# Board_760032v2.net
KiCad netlist of a schematic drawn in EAGLE
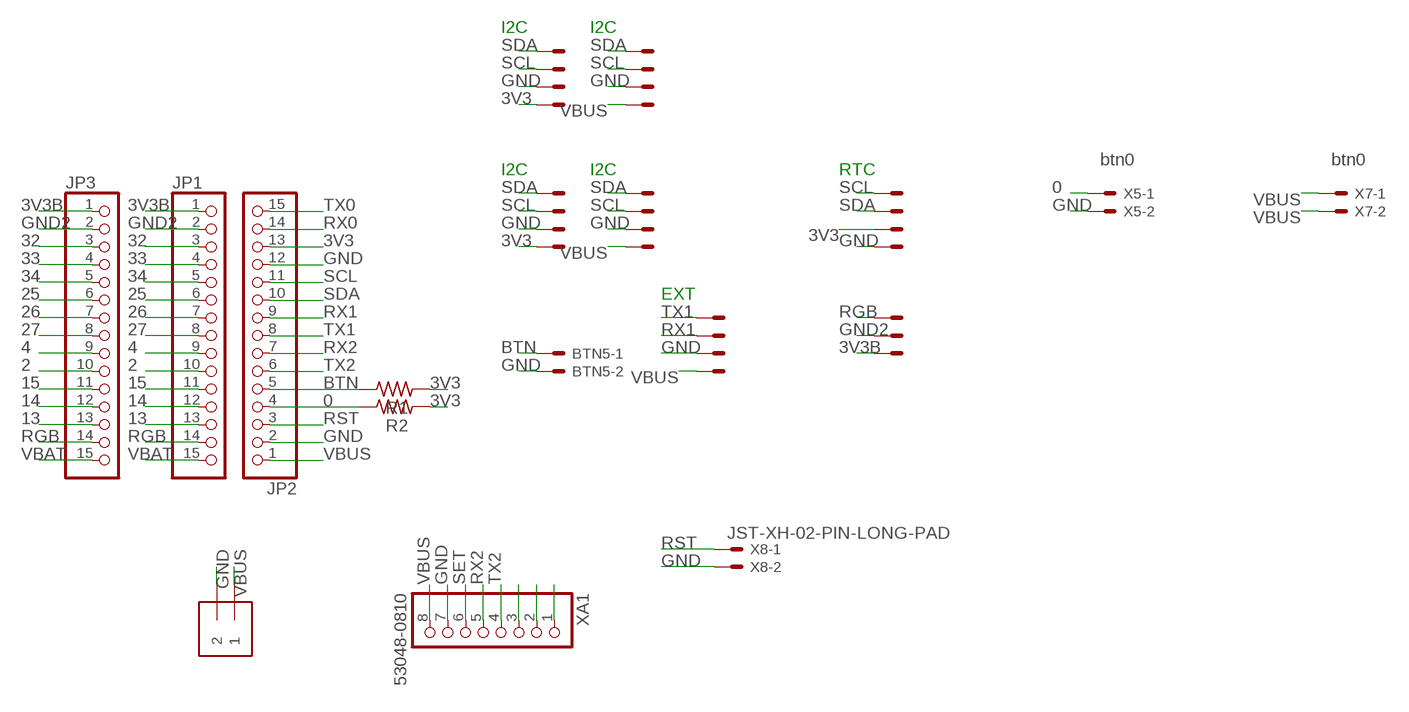
[diagram p0: schematic, sheet 1]

(export (version "E")
  (design (tool "Eeschema 10.0.6"))
  (components
    (comp (ref "BTN5")
      (value "JST-XH-02-PIN-LONG-PAD")
      (footprint "eagle-import:JST-XH-02-PACKAGE-LONG-PAD")
      (libsource (lib "eagle-import") (part "JST-XH-02-PIN-LONG-PAD"))
    )
    (comp (ref "J1")
      (value "1X2-3.5MM")
      (footprint "eagle-import:1X2-3.5MM")
      (libsource (lib "eagle-import") (part "1X2-3.5MM"))
    )
    (comp (ref "JP1")
      (value "PINHD-1X15")
      (footprint "eagle-import:1X15")
      (libsource (lib "eagle-import") (part "PINHD-1X15"))
    )
    (comp (ref "JP2")
      (value "PINHD-1X15")
      (footprint "eagle-import:1X15")
      (libsource (lib "eagle-import") (part "PINHD-1X15"))
    )
    (comp (ref "JP3")
      (value "PINHD-1X15")
      (footprint "eagle-import:1X15")
      (libsource (lib "eagle-import") (part "PINHD-1X15"))
    )
    (comp (ref "R1")
      (value "R-US_0207/7")
      (footprint "eagle-import:0207_7")
      (libsource (lib "eagle-import") (part "R-US_0207/7"))
    )
    (comp (ref "R2")
      (value "R-US_0207/7")
      (footprint "eagle-import:0207_7")
      (libsource (lib "eagle-import") (part "R-US_0207/7"))
    )
    (comp (ref "RTC")
      (value "JST-XH-04-PIN-LONG-PAD")
      (footprint "eagle-import:JST-XH-04-PACKAGE-LONG-PAD")
      (libsource (lib "eagle-import") (part "JST-XH-04-PIN-LONG-PAD"))
    )
    (comp (ref "X1")
      (value "JST-XH-04-PIN-LONG-PAD")
      (footprint "eagle-import:JST-XH-04-PACKAGE-LONG-PAD")
      (libsource (lib "eagle-import") (part "JST-XH-04-PIN-LONG-PAD"))
    )
    (comp (ref "X2")
      (value "JST-XH-04-PIN-LONG-PAD")
      (footprint "eagle-import:JST-XH-04-PACKAGE-LONG-PAD")
      (libsource (lib "eagle-import") (part "JST-XH-04-PIN-LONG-PAD"))
    )
    (comp (ref "X3")
      (value "JST-XH-04-PIN-LONG-PAD")
      (footprint "eagle-import:JST-XH-04-PACKAGE-LONG-PAD")
      (libsource (lib "eagle-import") (part "JST-XH-04-PIN-LONG-PAD"))
    )
    (comp (ref "X4")
      (value "JST-XH-03-PIN-LONG-PAD")
      (footprint "eagle-import:JST-XH-03-PACKAGE-LONG-PAD")
      (libsource (lib "eagle-import") (part "JST-XH-03-PIN-LONG-PAD"))
    )
    (comp (ref "X5")
      (value "btn0")
      (footprint "eagle-import:JST-XH-02-PACKAGE-LONG-PAD")
      (libsource (lib "eagle-import") (part "JST-XH-02-PIN-LONG-PAD"))
    )
    (comp (ref "X6")
      (value "JST-XH-04-PIN-LONG-PAD")
      (footprint "eagle-import:JST-XH-04-PACKAGE-LONG-PAD")
      (libsource (lib "eagle-import") (part "JST-XH-04-PIN-LONG-PAD"))
    )
    (comp (ref "X7")
      (value "btn0")
      (footprint "eagle-import:JST-XH-02-PACKAGE-LONG-PAD")
      (libsource (lib "eagle-import") (part "JST-XH-02-PIN-LONG-PAD"))
    )
    (comp (ref "X8")
      (value "JST-XH-02-PIN-LONG-PAD")
      (footprint "eagle-import:JST-XH-02-PACKAGE-LONG-PAD")
      (libsource (lib "eagle-import") (part "JST-XH-02-PIN-LONG-PAD"))
    )
    (comp (ref "X9")
      (value "JST-XH-04-PIN-LONG-PAD")
      (footprint "eagle-import:JST-XH-04-PACKAGE-LONG-PAD")
      (libsource (lib "eagle-import") (part "JST-XH-04-PIN-LONG-PAD"))
    )
    (comp (ref "XA1")
      (value "53048-0810")
      (footprint "eagle-import:MOLEX_53048-0810")
      (fields (field (name "MF") "Molex"))
      (libsource (lib "eagle-import") (part "53048-0810"))
    )
  )
  (nets
    (net (code "1") (name "/0") (class "Default")
      (node (ref "JP2") (pin "4") (pinfunction "4_4") (pintype "passive"))
      (node (ref "R2") (pin "1") (pinfunction "1_1") (pintype "passive"))
      (node (ref "X5") (pin "1") (pinfunction "S_1") (pintype "passive"))
    )
    (net (code "2") (name "/2") (class "Default")
      (node (ref "JP1") (pin "10") (pinfunction "10_10") (pintype "passive"))
      (node (ref "JP3") (pin "10") (pinfunction "10_10") (pintype "passive"))
    )
    (net (code "3") (name "/3V3") (class "Default")
      (node (ref "JP2") (pin "13") (pinfunction "13_13") (pintype "passive"))
      (node (ref "R1") (pin "2") (pinfunction "2_2") (pintype "passive"))
      (node (ref "R2") (pin "2") (pinfunction "2_2") (pintype "passive"))
      (node (ref "RTC") (pin "3") (pinfunction "S_3") (pintype "passive"))
      (node (ref "X1") (pin "4") (pinfunction "S_4") (pintype "passive"))
      (node (ref "X3") (pin "4") (pinfunction "S_4") (pintype "passive"))
    )
    (net (code "4") (name "/3V3B") (class "Default")
      (node (ref "JP1") (pin "1") (pinfunction "1_1") (pintype "passive"))
      (node (ref "JP3") (pin "1") (pinfunction "1_1") (pintype "passive"))
      (node (ref "X4") (pin "3") (pinfunction "S_3") (pintype "passive"))
    )
    (net (code "5") (name "/4") (class "Default")
      (node (ref "JP1") (pin "9") (pinfunction "9_9") (pintype "passive"))
      (node (ref "JP3") (pin "9") (pinfunction "9_9") (pintype "passive"))
    )
    (net (code "6") (name "/13") (class "Default")
      (node (ref "JP1") (pin "13") (pinfunction "13_13") (pintype "passive"))
      (node (ref "JP3") (pin "13") (pinfunction "13_13") (pintype "passive"))
    )
    (net (code "7") (name "/14") (class "Default")
      (node (ref "JP1") (pin "12") (pinfunction "12_12") (pintype "passive"))
      (node (ref "JP3") (pin "12") (pinfunction "12_12") (pintype "passive"))
    )
    (net (code "8") (name "/15") (class "Default")
      (node (ref "JP1") (pin "11") (pinfunction "11_11") (pintype "passive"))
      (node (ref "JP3") (pin "11") (pinfunction "11_11") (pintype "passive"))
    )
    (net (code "9") (name "/25") (class "Default")
      (node (ref "JP1") (pin "6") (pinfunction "6_6") (pintype "passive"))
      (node (ref "JP3") (pin "6") (pinfunction "6_6") (pintype "passive"))
    )
    (net (code "10") (name "/26") (class "Default")
      (node (ref "JP1") (pin "7") (pinfunction "7_7") (pintype "passive"))
      (node (ref "JP3") (pin "7") (pinfunction "7_7") (pintype "passive"))
    )
    (net (code "11") (name "/27") (class "Default")
      (node (ref "JP1") (pin "8") (pinfunction "8_8") (pintype "passive"))
      (node (ref "JP3") (pin "8") (pinfunction "8_8") (pintype "passive"))
    )
    (net (code "12") (name "/32") (class "Default")
      (node (ref "JP1") (pin "3") (pinfunction "3_3") (pintype "passive"))
      (node (ref "JP3") (pin "3") (pinfunction "3_3") (pintype "passive"))
    )
    (net (code "13") (name "/33") (class "Default")
      (node (ref "JP1") (pin "4") (pinfunction "4_4") (pintype "passive"))
      (node (ref "JP3") (pin "4") (pinfunction "4_4") (pintype "passive"))
    )
    (net (code "14") (name "/34") (class "Default")
      (node (ref "JP1") (pin "5") (pinfunction "5_5") (pintype "passive"))
      (node (ref "JP3") (pin "5") (pinfunction "5_5") (pintype "passive"))
    )
    (net (code "15") (name "/BTN") (class "Default")
      (node (ref "BTN5") (pin "1") (pinfunction "S_1") (pintype "passive"))
      (node (ref "JP2") (pin "5") (pinfunction "5_5") (pintype "passive"))
      (node (ref "R1") (pin "1") (pinfunction "1_1") (pintype "passive"))
    )
    (net (code "16") (name "/GND") (class "Default")
      (node (ref "BTN5") (pin "2") (pinfunction "S_2") (pintype "passive"))
      (node (ref "J1") (pin "2") (pinfunction "2_2") (pintype "passive"))
      (node (ref "JP2") (pin "12") (pinfunction "12_12") (pintype "passive"))
      (node (ref "JP2") (pin "2") (pinfunction "2_2") (pintype "passive"))
      (node (ref "RTC") (pin "4") (pinfunction "S_4") (pintype "passive"))
      (node (ref "X1") (pin "3") (pinfunction "S_3") (pintype "passive"))
      (node (ref "X2") (pin "3") (pinfunction "S_3") (pintype "passive"))
      (node (ref "X3") (pin "3") (pinfunction "S_3") (pintype "passive"))
      (node (ref "X5") (pin "2") (pinfunction "S_2") (pintype "passive"))
      (node (ref "X6") (pin "3") (pinfunction "S_3") (pintype "passive"))
      (node (ref "X8") (pin "2") (pinfunction "S_2") (pintype "passive"))
      (node (ref "X9") (pin "3") (pinfunction "S_3") (pintype "passive"))
      (node (ref "XA1") (pin "7") (pinfunction "7_7") (pintype "passive"))
    )
    (net (code "17") (name "/GND2") (class "Default")
      (node (ref "JP1") (pin "2") (pinfunction "2_2") (pintype "passive"))
      (node (ref "JP3") (pin "2") (pinfunction "2_2") (pintype "passive"))
      (node (ref "X4") (pin "2") (pinfunction "S_2") (pintype "passive"))
    )
    (net (code "18") (name "/RGB") (class "Default")
      (node (ref "JP1") (pin "14") (pinfunction "14_14") (pintype "passive"))
      (node (ref "JP3") (pin "14") (pinfunction "14_14") (pintype "passive"))
      (node (ref "X4") (pin "1") (pinfunction "S_1") (pintype "passive"))
    )
    (net (code "19") (name "/RST") (class "Default")
      (node (ref "JP2") (pin "3") (pinfunction "3_3") (pintype "passive"))
      (node (ref "X8") (pin "1") (pinfunction "S_1") (pintype "passive"))
    )
    (net (code "20") (name "/RX0") (class "Default")
      (node (ref "JP2") (pin "14") (pinfunction "14_14") (pintype "passive"))
    )
    (net (code "21") (name "/RX1") (class "Default")
      (node (ref "JP2") (pin "9") (pinfunction "9_9") (pintype "passive"))
      (node (ref "X6") (pin "2") (pinfunction "S_2") (pintype "passive"))
    )
    (net (code "22") (name "/RX2") (class "Default")
      (node (ref "JP2") (pin "7") (pinfunction "7_7") (pintype "passive"))
      (node (ref "XA1") (pin "5") (pinfunction "5_5") (pintype "passive"))
    )
    (net (code "23") (name "/SCL") (class "Default")
      (node (ref "JP2") (pin "11") (pinfunction "11_11") (pintype "passive"))
      (node (ref "RTC") (pin "1") (pinfunction "S_1") (pintype "passive"))
      (node (ref "X1") (pin "2") (pinfunction "S_2") (pintype "passive"))
      (node (ref "X2") (pin "2") (pinfunction "S_2") (pintype "passive"))
      (node (ref "X3") (pin "2") (pinfunction "S_2") (pintype "passive"))
      (node (ref "X9") (pin "2") (pinfunction "S_2") (pintype "passive"))
    )
    (net (code "24") (name "/SDA") (class "Default")
      (node (ref "JP2") (pin "10") (pinfunction "10_10") (pintype "passive"))
      (node (ref "RTC") (pin "2") (pinfunction "S_2") (pintype "passive"))
      (node (ref "X1") (pin "1") (pinfunction "S_1") (pintype "passive"))
      (node (ref "X2") (pin "1") (pinfunction "S_1") (pintype "passive"))
      (node (ref "X3") (pin "1") (pinfunction "S_1") (pintype "passive"))
      (node (ref "X9") (pin "1") (pinfunction "S_1") (pintype "passive"))
    )
    (net (code "25") (name "/SET") (class "Default")
      (node (ref "XA1") (pin "6") (pinfunction "6_6") (pintype "passive"))
    )
    (net (code "26") (name "/TX0") (class "Default")
      (node (ref "JP2") (pin "15") (pinfunction "15_15") (pintype "passive"))
    )
    (net (code "27") (name "/TX1") (class "Default")
      (node (ref "JP2") (pin "8") (pinfunction "8_8") (pintype "passive"))
      (node (ref "X6") (pin "1") (pinfunction "S_1") (pintype "passive"))
    )
    (net (code "28") (name "/TX2") (class "Default")
      (node (ref "JP2") (pin "6") (pinfunction "6_6") (pintype "passive"))
      (node (ref "XA1") (pin "4") (pinfunction "4_4") (pintype "passive"))
    )
    (net (code "29") (name "/VBAT") (class "Default")
      (node (ref "JP1") (pin "15") (pinfunction "15_15") (pintype "passive"))
      (node (ref "JP3") (pin "15") (pinfunction "15_15") (pintype "passive"))
    )
    (net (code "30") (name "/VBUS") (class "Default")
      (node (ref "J1") (pin "1") (pinfunction "1_1") (pintype "passive"))
      (node (ref "JP2") (pin "1") (pinfunction "1_1") (pintype "passive"))
      (node (ref "X2") (pin "4") (pinfunction "S_4") (pintype "passive"))
      (node (ref "X6") (pin "4") (pinfunction "S_4") (pintype "passive"))
      (node (ref "X7") (pin "1") (pinfunction "S_1") (pintype "passive"))
      (node (ref "X7") (pin "2") (pinfunction "S_2") (pintype "passive"))
      (node (ref "X9") (pin "4") (pinfunction "S_4") (pintype "passive"))
      (node (ref "XA1") (pin "8") (pinfunction "8_8") (pintype "passive"))
    )
    (net (code "31") (name "unconnected-(XA1-Pad1)") (class "Default")
      (node (ref "XA1") (pin "1") (pinfunction "1_1") (pintype "passive"))
    )
    (net (code "32") (name "unconnected-(XA1-Pad2)") (class "Default")
      (node (ref "XA1") (pin "2") (pinfunction "2_2") (pintype "passive"))
    )
    (net (code "33") (name "unconnected-(XA1-Pad3)") (class "Default")
      (node (ref "XA1") (pin "3") (pinfunction "3_3") (pintype "passive"))
    )
  )
)
